# RX.net
KiCad netlist of a schematic drawn in EAGLE
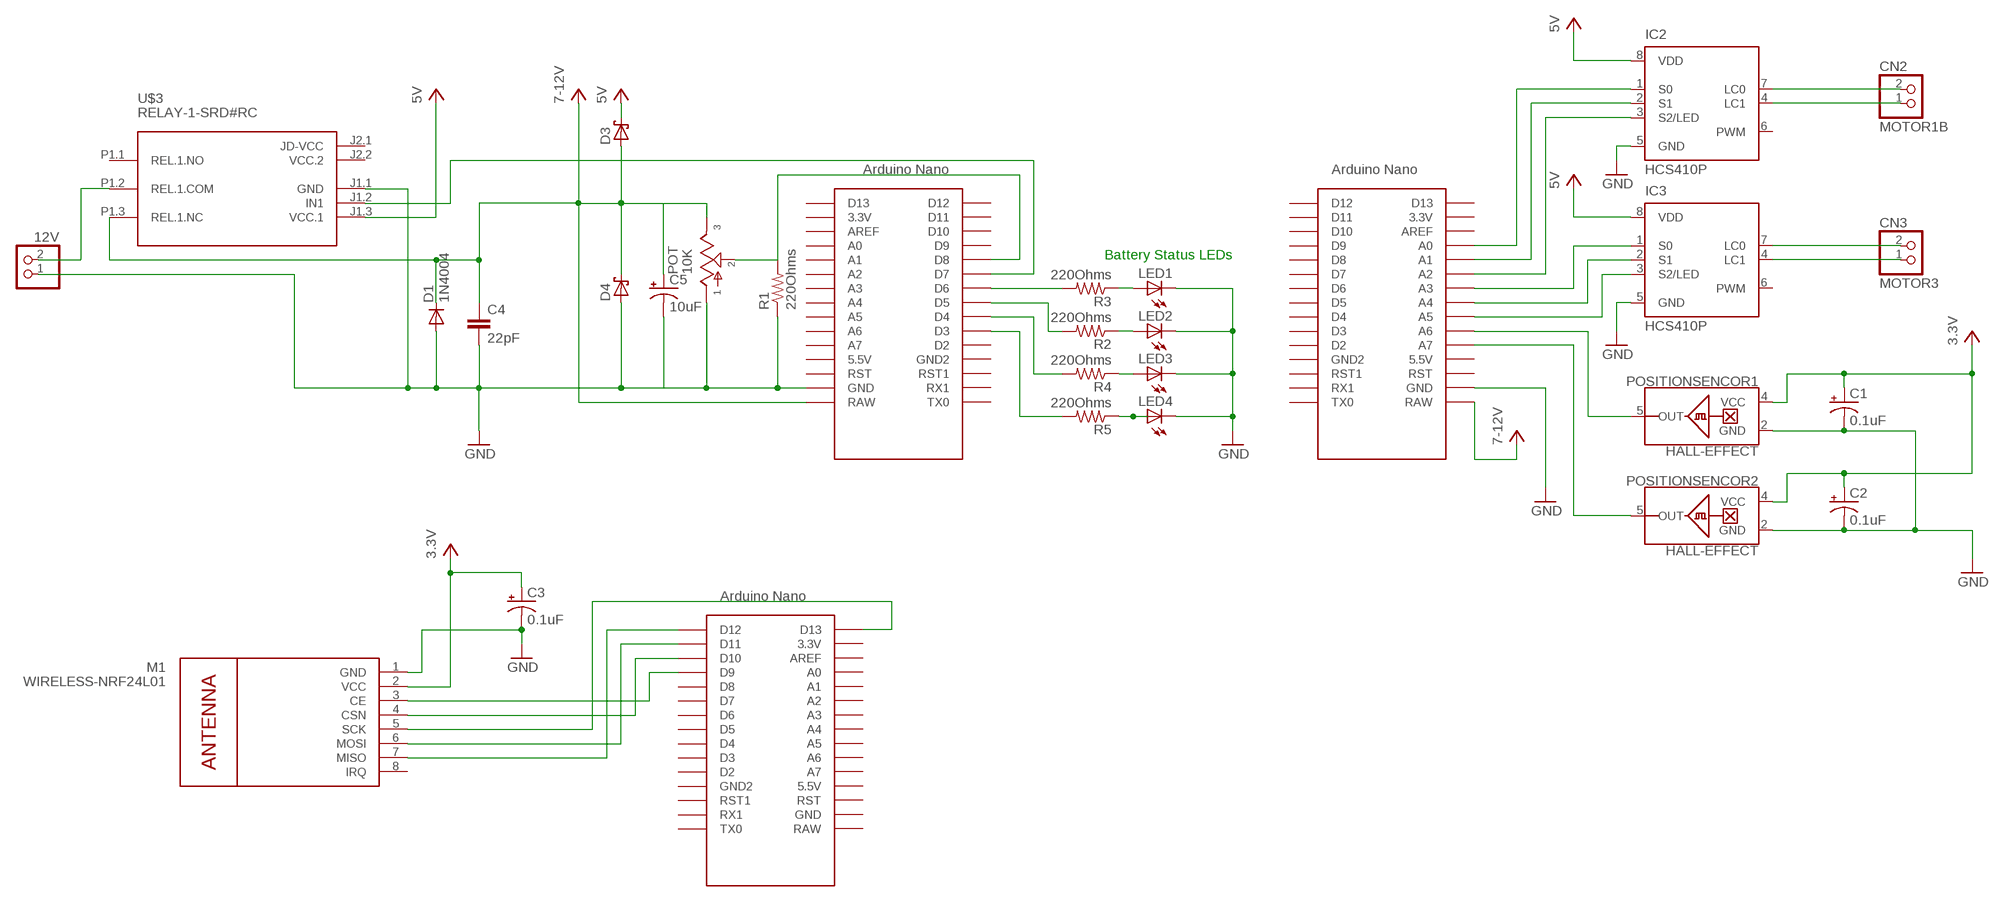
[diagram p0: schematic, sheet 1]

(export (version "E")
  (design (tool "Eeschema 10.0.6"))
  (components
    (comp (ref "12V")
      (value "JST_2PIN-SMT")
      (footprint "eagle-import:JST-PH-2-SMT")
      (libsource (lib "eagle-import") (part "JST_2PIN-SMT"))
    )
    (comp (ref "C1")
      (value "0.1uF")
      (footprint "eagle-import:EIA3216")
      (libsource (lib "eagle-import") (part "CAP_POL1206"))
    )
    (comp (ref "C2")
      (value "0.1uF")
      (footprint "eagle-import:EIA3216")
      (libsource (lib "eagle-import") (part "CAP_POL1206"))
    )
    (comp (ref "C3")
      (value "0.1uF")
      (footprint "eagle-import:EIA3216")
      (libsource (lib "eagle-import") (part "CAP_POL1206"))
    )
    (comp (ref "C4")
      (value "22pF")
      (footprint "eagle-import:C2.5-3")
      (libsource (lib "eagle-import") (part "C2,5-3"))
    )
    (comp (ref "C5")
      (value "10uF")
      (footprint "eagle-import:EIA3216")
      (libsource (lib "eagle-import") (part "CAP_POL1206"))
    )
    (comp (ref "CN2")
      (value "MOTOR1B")
      (footprint "eagle-import:JST-PH-2-SMT")
      (libsource (lib "eagle-import") (part "JST_2PIN-SMT"))
    )
    (comp (ref "CN3")
      (value "MOTOR3")
      (footprint "eagle-import:JST-PH-2-SMT")
      (libsource (lib "eagle-import") (part "JST_2PIN-SMT"))
    )
    (comp (ref "D1")
      (value "1N4004")
      (footprint "eagle-import:DO41-10")
      (libsource (lib "eagle-import") (part "1N4004"))
    )
    (comp (ref "D3")
      (value "SCHOTTKY-DIODEAG")
      (footprint "eagle-import:AG")
      (libsource (lib "eagle-import") (part "SCHOTTKY-DIODEAG"))
    )
    (comp (ref "D4")
      (value "SCHOTTKY-DIODEAG")
      (footprint "eagle-import:AG")
      (libsource (lib "eagle-import") (part "SCHOTTKY-DIODEAG"))
    )
    (comp (ref "IC2")
      (value "HCS410P")
      (footprint "eagle-import:DIL8")
      (fields (field (name "MF") "MICROCHIP") (field (name "MPN") "HCS410-I/P"))
      (libsource (lib "eagle-import") (part "HCS410P"))
    )
    (comp (ref "IC3")
      (value "HCS410P")
      (footprint "eagle-import:DIL8")
      (fields (field (name "MF") "MICROCHIP") (field (name "MPN") "HCS410-I/P"))
      (libsource (lib "eagle-import") (part "HCS410P"))
    )
    (comp (ref "LED1")
      (value "LED")
      (footprint "eagle-import:SMARTLED-TTW")
      (libsource (lib "eagle-import") (part "LED"))
    )
    (comp (ref "LED2")
      (value "LED")
      (footprint "eagle-import:SMARTLED-TTW")
      (libsource (lib "eagle-import") (part "LED"))
    )
    (comp (ref "LED3")
      (value "LED")
      (footprint "eagle-import:SMARTLED-TTW")
      (libsource (lib "eagle-import") (part "LED"))
    )
    (comp (ref "LED4")
      (value "LED")
      (footprint "eagle-import:SMARTLED-TTW")
      (libsource (lib "eagle-import") (part "LED"))
    )
    (comp (ref "M1")
      (value "WIRELESS-NRF24L01")
      (footprint "eagle-import:WIRELESS-NRF24L01")
      (libsource (lib "eagle-import") (part "WIRELESS-NRF24L01"))
    )
    (comp (ref "POSITIONSENCOR1")
      (value "HALL-EFFECT")
      (footprint "eagle-import:SC70")
      (libsource (lib "eagle-import") (part "HALL-EFFECT"))
    )
    (comp (ref "POSITIONSENCOR2")
      (value "HALL-EFFECT")
      (footprint "eagle-import:SC70")
      (libsource (lib "eagle-import") (part "HALL-EFFECT"))
    )
    (comp (ref "POT")
      (value "10K")
      (footprint "eagle-import:POT")
      (libsource (lib "eagle-import") (part "POT"))
    )
    (comp (ref "R1")
      (value "220Ohms")
      (footprint "eagle-import:0204V")
      (libsource (lib "eagle-import") (part "R-US_0204/2V"))
    )
    (comp (ref "R2")
      (value "220Ohms")
      (footprint "eagle-import:0204V")
      (libsource (lib "eagle-import") (part "R-US_0204/2V"))
    )
    (comp (ref "R3")
      (value "220Ohms")
      (footprint "eagle-import:0204V")
      (libsource (lib "eagle-import") (part "R-US_0204/2V"))
    )
    (comp (ref "R4")
      (value "220Ohms")
      (footprint "eagle-import:0204V")
      (libsource (lib "eagle-import") (part "R-US_0204/2V"))
    )
    (comp (ref "R5")
      (value "220Ohms")
      (footprint "eagle-import:0204V")
      (libsource (lib "eagle-import") (part "R-US_0204/2V"))
    )
    (comp (ref "U$1")
      (value "NANO")
      (footprint "eagle-import:NANO")
      (libsource (lib "eagle-import") (part "NANO"))
    )
    (comp (ref "U$2")
      (value "NANO")
      (footprint "eagle-import:NANO")
      (libsource (lib "eagle-import") (part "NANO"))
    )
    (comp (ref "U$3")
      (value "RELAY-1-SRD#RC")
      (footprint "eagle-import:RELAY-1-SRD#RC")
      (libsource (lib "eagle-import") (part "RELAY-1-SRD#RC"))
    )
    (comp (ref "U$4")
      (value "NANO")
      (footprint "eagle-import:NANO")
      (libsource (lib "eagle-import") (part "NANO"))
    )
  )
  (nets
    (net (code "1") (name "/VCC.2") (class "Default")
      (node (ref "U$3") (pin "J2.2") (pinfunction "VCC.2_J2.2") (pintype "power_in"))
    )
    (net (code "2") (name "3.3V") (class "Default")
      (node (ref "C1") (pin "A") (pinfunction "+_A") (pintype "passive"))
      (node (ref "C2") (pin "A") (pinfunction "+_A") (pintype "passive"))
      (node (ref "C3") (pin "A") (pinfunction "+_A") (pintype "passive"))
      (node (ref "C4") (pin "1") (pinfunction "1_1") (pintype "passive"))
      (node (ref "C5") (pin "A") (pinfunction "+_A") (pintype "passive"))
      (node (ref "D1") (pin "C") (pinfunction "C_C") (pintype "passive"))
      (node (ref "D3") (pin "A") (pinfunction "A_A") (pintype "passive"))
      (node (ref "D3") (pin "C") (pinfunction "C_C") (pintype "passive"))
      (node (ref "D4") (pin "C") (pinfunction "C_C") (pintype "passive"))
      (node (ref "IC2") (pin "8") (pinfunction "VDD_8") (pintype "power_in"))
      (node (ref "IC3") (pin "8") (pinfunction "VDD_8") (pintype "power_in"))
      (node (ref "M1") (pin "2") (pinfunction "VCC_2") (pintype "power_in"))
      (node (ref "POSITIONSENCOR1") (pin "4") (pinfunction "VCC_4") (pintype "bidirectional"))
      (node (ref "POSITIONSENCOR2") (pin "4") (pinfunction "VCC_4") (pintype "bidirectional"))
      (node (ref "POT") (pin "3") (pinfunction "3_3") (pintype "passive"))
      (node (ref "U$1") (pin "RAW") (pinfunction "RAW_RAW") (pintype "bidirectional"))
      (node (ref "U$2") (pin "RAW") (pinfunction "RAW_RAW") (pintype "bidirectional"))
      (node (ref "U$3") (pin "J1.3") (pinfunction "VCC.1_J1.3") (pintype "power_in"))
      (node (ref "U$3") (pin "P1.3") (pinfunction "REL.1.NC_P1.3") (pintype "bidirectional"))
    )
    (net (code "3") (name "GND") (class "Default")
      (node (ref "12V") (pin "1") (pinfunction "2_1") (pintype "passive"))
      (node (ref "C1") (pin "C") (pinfunction "-_C") (pintype "passive"))
      (node (ref "C2") (pin "C") (pinfunction "-_C") (pintype "passive"))
      (node (ref "C3") (pin "C") (pinfunction "-_C") (pintype "passive"))
      (node (ref "C4") (pin "2") (pinfunction "2_2") (pintype "passive"))
      (node (ref "C5") (pin "C") (pinfunction "-_C") (pintype "passive"))
      (node (ref "D1") (pin "A") (pinfunction "A_A") (pintype "passive"))
      (node (ref "D4") (pin "A") (pinfunction "A_A") (pintype "passive"))
      (node (ref "IC2") (pin "5") (pinfunction "GND_5") (pintype "power_in"))
      (node (ref "IC3") (pin "5") (pinfunction "GND_5") (pintype "power_in"))
      (node (ref "LED1") (pin "C@1") (pinfunction "C_C@1") (pintype "passive"))
      (node (ref "LED2") (pin "C@1") (pinfunction "C_C@1") (pintype "passive"))
      (node (ref "LED3") (pin "C@1") (pinfunction "C_C@1") (pintype "passive"))
      (node (ref "LED4") (pin "C@1") (pinfunction "C_C@1") (pintype "passive"))
      (node (ref "M1") (pin "1") (pinfunction "GND_1") (pintype "power_in"))
      (node (ref "POSITIONSENCOR1") (pin "2") (pinfunction "GND_2") (pintype "bidirectional"))
      (node (ref "POSITIONSENCOR2") (pin "2") (pinfunction "GND_2") (pintype "bidirectional"))
      (node (ref "POT") (pin "1") (pinfunction "1_1") (pintype "passive"))
      (node (ref "R1") (pin "1") (pinfunction "1_1") (pintype "passive"))
      (node (ref "U$1") (pin "GND") (pinfunction "GND_GND") (pintype "bidirectional"))
      (node (ref "U$2") (pin "GND") (pinfunction "GND_GND") (pintype "bidirectional"))
      (node (ref "U$3") (pin "J1.1") (pinfunction "GND_J1.1") (pintype "power_in"))
    )
    (net (code "4") (name "Net-(12V-1)") (class "Default")
      (node (ref "12V") (pin "2") (pinfunction "1_2") (pintype "passive"))
      (node (ref "U$3") (pin "P1.2") (pinfunction "REL.1.COM_P1.2") (pintype "bidirectional"))
    )
    (net (code "5") (name "Net-(CN2-1)") (class "Default")
      (node (ref "CN2") (pin "2") (pinfunction "1_2") (pintype "passive"))
      (node (ref "IC2") (pin "7") (pinfunction "LC0_7") (pintype "bidirectional"))
    )
    (net (code "6") (name "Net-(CN2-2)") (class "Default")
      (node (ref "CN2") (pin "1") (pinfunction "2_1") (pintype "passive"))
      (node (ref "IC2") (pin "4") (pinfunction "LC1_4") (pintype "bidirectional"))
    )
    (net (code "7") (name "Net-(CN3-1)") (class "Default")
      (node (ref "CN3") (pin "2") (pinfunction "1_2") (pintype "passive"))
      (node (ref "IC3") (pin "7") (pinfunction "LC0_7") (pintype "bidirectional"))
    )
    (net (code "8") (name "Net-(CN3-2)") (class "Default")
      (node (ref "CN3") (pin "1") (pinfunction "2_1") (pintype "passive"))
      (node (ref "IC3") (pin "4") (pinfunction "LC1_4") (pintype "bidirectional"))
    )
    (net (code "9") (name "Net-(IC2-S0)") (class "Default")
      (node (ref "IC2") (pin "1") (pinfunction "S0_1") (pintype "input"))
      (node (ref "U$1") (pin "A0") (pinfunction "A0_A0") (pintype "bidirectional"))
    )
    (net (code "10") (name "Net-(IC2-S1)") (class "Default")
      (node (ref "IC2") (pin "2") (pinfunction "S1_2") (pintype "input"))
      (node (ref "U$1") (pin "A1") (pinfunction "A1_A1") (pintype "bidirectional"))
    )
    (net (code "11") (name "Net-(IC2-S2{slash}LED)") (class "Default")
      (node (ref "IC2") (pin "3") (pinfunction "S2/LED_3") (pintype "bidirectional"))
      (node (ref "U$1") (pin "A2") (pinfunction "A2_A2") (pintype "bidirectional"))
    )
    (net (code "12") (name "Net-(IC3-S0)") (class "Default")
      (node (ref "IC3") (pin "1") (pinfunction "S0_1") (pintype "input"))
      (node (ref "U$1") (pin "A3") (pinfunction "A3_A3") (pintype "bidirectional"))
    )
    (net (code "13") (name "Net-(IC3-S1)") (class "Default")
      (node (ref "IC3") (pin "2") (pinfunction "S1_2") (pintype "input"))
      (node (ref "U$1") (pin "A4") (pinfunction "A4_A4") (pintype "bidirectional"))
    )
    (net (code "14") (name "Net-(IC3-S2{slash}LED)") (class "Default")
      (node (ref "IC3") (pin "3") (pinfunction "S2/LED_3") (pintype "bidirectional"))
      (node (ref "U$1") (pin "A5") (pinfunction "A5_A5") (pintype "bidirectional"))
    )
    (net (code "15") (name "Net-(LED1-A)") (class "Default")
      (node (ref "LED1") (pin "A@1") (pinfunction "A_A@1") (pintype "passive"))
      (node (ref "R3") (pin "1") (pinfunction "1_1") (pintype "passive"))
    )
    (net (code "16") (name "Net-(LED2-A)") (class "Default")
      (node (ref "LED2") (pin "A@1") (pinfunction "A_A@1") (pintype "passive"))
      (node (ref "R2") (pin "1") (pinfunction "1_1") (pintype "passive"))
    )
    (net (code "17") (name "Net-(LED3-A)") (class "Default")
      (node (ref "LED3") (pin "A@1") (pinfunction "A_A@1") (pintype "passive"))
      (node (ref "R4") (pin "1") (pinfunction "1_1") (pintype "passive"))
    )
    (net (code "18") (name "Net-(LED4-A)") (class "Default")
      (node (ref "LED4") (pin "A@1") (pinfunction "A_A@1") (pintype "passive"))
      (node (ref "R5") (pin "1") (pinfunction "1_1") (pintype "passive"))
    )
    (net (code "19") (name "Net-(M1-CE)") (class "Default")
      (node (ref "M1") (pin "3") (pinfunction "CE_3") (pintype "bidirectional"))
      (node (ref "U$4") (pin "D9") (pinfunction "D9_D9") (pintype "bidirectional"))
    )
    (net (code "20") (name "Net-(M1-CSN)") (class "Default")
      (node (ref "M1") (pin "4") (pinfunction "CSN_4") (pintype "bidirectional"))
      (node (ref "U$4") (pin "D10") (pinfunction "D10_D10") (pintype "bidirectional"))
    )
    (net (code "21") (name "Net-(M1-MISO)") (class "Default")
      (node (ref "M1") (pin "7") (pinfunction "MISO_7") (pintype "bidirectional"))
      (node (ref "U$4") (pin "D12") (pinfunction "D12_D12") (pintype "bidirectional"))
    )
    (net (code "22") (name "Net-(M1-MOSI)") (class "Default")
      (node (ref "M1") (pin "6") (pinfunction "MOSI_6") (pintype "bidirectional"))
      (node (ref "U$4") (pin "D11") (pinfunction "D11_D11") (pintype "bidirectional"))
    )
    (net (code "23") (name "Net-(M1-SCK)") (class "Default")
      (node (ref "M1") (pin "5") (pinfunction "SCK_5") (pintype "bidirectional"))
      (node (ref "U$4") (pin "D13") (pinfunction "D13_D13") (pintype "bidirectional"))
    )
    (net (code "24") (name "Net-(POSITIONSENCOR1-OUT)") (class "Default")
      (node (ref "POSITIONSENCOR1") (pin "5") (pinfunction "OUT_5") (pintype "bidirectional"))
      (node (ref "U$1") (pin "A6") (pinfunction "A6_A6") (pintype "bidirectional"))
    )
    (net (code "25") (name "Net-(POSITIONSENCOR2-OUT)") (class "Default")
      (node (ref "POSITIONSENCOR2") (pin "5") (pinfunction "OUT_5") (pintype "bidirectional"))
      (node (ref "U$1") (pin "A7") (pinfunction "A7_A7") (pintype "bidirectional"))
    )
    (net (code "26") (name "Net-(POT-Pad2)") (class "Default")
      (node (ref "POT") (pin "2") (pinfunction "2_2") (pintype "passive"))
      (node (ref "R1") (pin "2") (pinfunction "2_2") (pintype "passive"))
      (node (ref "U$2") (pin "D8") (pinfunction "D8_D8") (pintype "bidirectional"))
    )
    (net (code "27") (name "Net-(R2-Pad2)") (class "Default")
      (node (ref "R2") (pin "2") (pinfunction "2_2") (pintype "passive"))
      (node (ref "U$2") (pin "D5") (pinfunction "D5_D5") (pintype "bidirectional"))
    )
    (net (code "28") (name "Net-(R3-Pad2)") (class "Default")
      (node (ref "R3") (pin "2") (pinfunction "2_2") (pintype "passive"))
      (node (ref "U$2") (pin "D6") (pinfunction "D6_D6") (pintype "bidirectional"))
    )
    (net (code "29") (name "Net-(R4-Pad2)") (class "Default")
      (node (ref "R4") (pin "2") (pinfunction "2_2") (pintype "passive"))
      (node (ref "U$2") (pin "D4") (pinfunction "D4_D4") (pintype "bidirectional"))
    )
    (net (code "30") (name "Net-(R5-Pad2)") (class "Default")
      (node (ref "R5") (pin "2") (pinfunction "2_2") (pintype "passive"))
      (node (ref "U$2") (pin "D3") (pinfunction "D3_D3") (pintype "bidirectional"))
    )
    (net (code "31") (name "Net-(U$3-IN1)") (class "Default")
      (node (ref "U$2") (pin "D7") (pinfunction "D7_D7") (pintype "bidirectional"))
      (node (ref "U$3") (pin "J1.2") (pinfunction "IN1_J1.2") (pintype "bidirectional"))
    )
    (net (code "32") (name "unconnected-(IC2-PWM-Pad6)") (class "Default")
      (node (ref "IC2") (pin "6") (pinfunction "PWM_6") (pintype "bidirectional"))
    )
    (net (code "33") (name "unconnected-(IC3-PWM-Pad6)") (class "Default")
      (node (ref "IC3") (pin "6") (pinfunction "PWM_6") (pintype "bidirectional"))
    )
    (net (code "34") (name "unconnected-(M1-IRQ-Pad8)") (class "Default")
      (node (ref "M1") (pin "8") (pinfunction "IRQ_8") (pintype "bidirectional"))
    )
    (net (code "35") (name "unconnected-(U$1-5.5V-Pad5V)") (class "Default")
      (node (ref "U$1") (pin "5V") (pinfunction "5.5V_5V") (pintype "bidirectional"))
    )
    (net (code "36") (name "unconnected-(U$1-GND2-PadGND1)") (class "Default")
      (node (ref "U$1") (pin "GND1") (pinfunction "GND2_GND1") (pintype "bidirectional"))
    )
    (net (code "37") (name "unconnected-(U$1-Pad3.3V)") (class "Default")
      (node (ref "U$1") (pin "3.3V") (pinfunction "3.3V_3.3V") (pintype "bidirectional"))
    )
    (net (code "38") (name "unconnected-(U$1-PadAREF)") (class "Default")
      (node (ref "U$1") (pin "AREF") (pinfunction "AREF_AREF") (pintype "bidirectional"))
    )
    (net (code "39") (name "unconnected-(U$1-PadD2)") (class "Default")
      (node (ref "U$1") (pin "D2") (pinfunction "D2_D2") (pintype "bidirectional"))
    )
    (net (code "40") (name "unconnected-(U$1-PadD3)") (class "Default")
      (node (ref "U$1") (pin "D3") (pinfunction "D3_D3") (pintype "bidirectional"))
    )
    (net (code "41") (name "unconnected-(U$1-PadD4)") (class "Default")
      (node (ref "U$1") (pin "D4") (pinfunction "D4_D4") (pintype "bidirectional"))
    )
    (net (code "42") (name "unconnected-(U$1-PadD5)") (class "Default")
      (node (ref "U$1") (pin "D5") (pinfunction "D5_D5") (pintype "bidirectional"))
    )
    (net (code "43") (name "unconnected-(U$1-PadD6)") (class "Default")
      (node (ref "U$1") (pin "D6") (pinfunction "D6_D6") (pintype "bidirectional"))
    )
    (net (code "44") (name "unconnected-(U$1-PadD7)") (class "Default")
      (node (ref "U$1") (pin "D7") (pinfunction "D7_D7") (pintype "bidirectional"))
    )
    (net (code "45") (name "unconnected-(U$1-PadD8)") (class "Default")
      (node (ref "U$1") (pin "D8") (pinfunction "D8_D8") (pintype "bidirectional"))
    )
    (net (code "46") (name "unconnected-(U$1-PadD9)") (class "Default")
      (node (ref "U$1") (pin "D9") (pinfunction "D9_D9") (pintype "bidirectional"))
    )
    (net (code "47") (name "unconnected-(U$1-PadD10)") (class "Default")
      (node (ref "U$1") (pin "D10") (pinfunction "D10_D10") (pintype "bidirectional"))
    )
    (net (code "48") (name "unconnected-(U$1-PadD11)") (class "Default")
      (node (ref "U$1") (pin "D11") (pinfunction "D11_D11") (pintype "bidirectional"))
    )
    (net (code "49") (name "unconnected-(U$1-PadD12)") (class "Default")
      (node (ref "U$1") (pin "D12") (pinfunction "D12_D12") (pintype "bidirectional"))
    )
    (net (code "50") (name "unconnected-(U$1-PadD13)") (class "Default")
      (node (ref "U$1") (pin "D13") (pinfunction "D13_D13") (pintype "bidirectional"))
    )
    (net (code "51") (name "unconnected-(U$1-PadICSP1)") (class "Default")
      (node (ref "U$1") (pin "ICSP1") (pinfunction "ICSP1_ICSP1") (pintype "bidirectional"))
    )
    (net (code "52") (name "unconnected-(U$1-PadICSP2)") (class "Default")
      (node (ref "U$1") (pin "ICSP2") (pinfunction "ICSP2_ICSP2") (pintype "bidirectional"))
    )
    (net (code "53") (name "unconnected-(U$1-PadICSP3)") (class "Default")
      (node (ref "U$1") (pin "ICSP3") (pinfunction "ICSP3_ICSP3") (pintype "bidirectional"))
    )
    (net (code "54") (name "unconnected-(U$1-PadICSP4)") (class "Default")
      (node (ref "U$1") (pin "ICSP4") (pinfunction "ICSP4_ICSP4") (pintype "bidirectional"))
    )
    (net (code "55") (name "unconnected-(U$1-PadICSP5)") (class "Default")
      (node (ref "U$1") (pin "ICSP5") (pinfunction "ICSP5_ICSP5") (pintype "bidirectional"))
    )
    (net (code "56") (name "unconnected-(U$1-PadICSP6)") (class "Default")
      (node (ref "U$1") (pin "ICSP6") (pinfunction "ICSP6_ICSP6") (pintype "bidirectional"))
    )
    (net (code "57") (name "unconnected-(U$1-PadRST)") (class "Default")
      (node (ref "U$1") (pin "RST") (pinfunction "RST_RST") (pintype "bidirectional"))
    )
    (net (code "58") (name "unconnected-(U$1-PadRST1)") (class "Default")
      (node (ref "U$1") (pin "RST1") (pinfunction "RST1_RST1") (pintype "bidirectional"))
    )
    (net (code "59") (name "unconnected-(U$1-PadRX1)") (class "Default")
      (node (ref "U$1") (pin "RX1") (pinfunction "RX1_RX1") (pintype "bidirectional"))
    )
    (net (code "60") (name "unconnected-(U$1-PadTX0)") (class "Default")
      (node (ref "U$1") (pin "TX0") (pinfunction "TX0_TX0") (pintype "bidirectional"))
    )
    (net (code "61") (name "unconnected-(U$2-5.5V-Pad5V)") (class "Default")
      (node (ref "U$2") (pin "5V") (pinfunction "5.5V_5V") (pintype "bidirectional"))
    )
    (net (code "62") (name "unconnected-(U$2-GND2-PadGND1)") (class "Default")
      (node (ref "U$2") (pin "GND1") (pinfunction "GND2_GND1") (pintype "bidirectional"))
    )
    (net (code "63") (name "unconnected-(U$2-Pad3.3V)") (class "Default")
      (node (ref "U$2") (pin "3.3V") (pinfunction "3.3V_3.3V") (pintype "bidirectional"))
    )
    (net (code "64") (name "unconnected-(U$2-PadA0)") (class "Default")
      (node (ref "U$2") (pin "A0") (pinfunction "A0_A0") (pintype "bidirectional"))
    )
    (net (code "65") (name "unconnected-(U$2-PadA1)") (class "Default")
      (node (ref "U$2") (pin "A1") (pinfunction "A1_A1") (pintype "bidirectional"))
    )
    (net (code "66") (name "unconnected-(U$2-PadA2)") (class "Default")
      (node (ref "U$2") (pin "A2") (pinfunction "A2_A2") (pintype "bidirectional"))
    )
    (net (code "67") (name "unconnected-(U$2-PadA3)") (class "Default")
      (node (ref "U$2") (pin "A3") (pinfunction "A3_A3") (pintype "bidirectional"))
    )
    (net (code "68") (name "unconnected-(U$2-PadA4)") (class "Default")
      (node (ref "U$2") (pin "A4") (pinfunction "A4_A4") (pintype "bidirectional"))
    )
    (net (code "69") (name "unconnected-(U$2-PadA5)") (class "Default")
      (node (ref "U$2") (pin "A5") (pinfunction "A5_A5") (pintype "bidirectional"))
    )
    (net (code "70") (name "unconnected-(U$2-PadA6)") (class "Default")
      (node (ref "U$2") (pin "A6") (pinfunction "A6_A6") (pintype "bidirectional"))
    )
    (net (code "71") (name "unconnected-(U$2-PadA7)") (class "Default")
      (node (ref "U$2") (pin "A7") (pinfunction "A7_A7") (pintype "bidirectional"))
    )
    (net (code "72") (name "unconnected-(U$2-PadAREF)") (class "Default")
      (node (ref "U$2") (pin "AREF") (pinfunction "AREF_AREF") (pintype "bidirectional"))
    )
    (net (code "73") (name "unconnected-(U$2-PadD2)") (class "Default")
      (node (ref "U$2") (pin "D2") (pinfunction "D2_D2") (pintype "bidirectional"))
    )
    (net (code "74") (name "unconnected-(U$2-PadD9)") (class "Default")
      (node (ref "U$2") (pin "D9") (pinfunction "D9_D9") (pintype "bidirectional"))
    )
    (net (code "75") (name "unconnected-(U$2-PadD10)") (class "Default")
      (node (ref "U$2") (pin "D10") (pinfunction "D10_D10") (pintype "bidirectional"))
    )
    (net (code "76") (name "unconnected-(U$2-PadD11)") (class "Default")
      (node (ref "U$2") (pin "D11") (pinfunction "D11_D11") (pintype "bidirectional"))
    )
    (net (code "77") (name "unconnected-(U$2-PadD12)") (class "Default")
      (node (ref "U$2") (pin "D12") (pinfunction "D12_D12") (pintype "bidirectional"))
    )
    (net (code "78") (name "unconnected-(U$2-PadD13)") (class "Default")
      (node (ref "U$2") (pin "D13") (pinfunction "D13_D13") (pintype "bidirectional"))
    )
    (net (code "79") (name "unconnected-(U$2-PadICSP1)") (class "Default")
      (node (ref "U$2") (pin "ICSP1") (pinfunction "ICSP1_ICSP1") (pintype "bidirectional"))
    )
    (net (code "80") (name "unconnected-(U$2-PadICSP2)") (class "Default")
      (node (ref "U$2") (pin "ICSP2") (pinfunction "ICSP2_ICSP2") (pintype "bidirectional"))
    )
    (net (code "81") (name "unconnected-(U$2-PadICSP3)") (class "Default")
      (node (ref "U$2") (pin "ICSP3") (pinfunction "ICSP3_ICSP3") (pintype "bidirectional"))
    )
    (net (code "82") (name "unconnected-(U$2-PadICSP4)") (class "Default")
      (node (ref "U$2") (pin "ICSP4") (pinfunction "ICSP4_ICSP4") (pintype "bidirectional"))
    )
    (net (code "83") (name "unconnected-(U$2-PadICSP5)") (class "Default")
      (node (ref "U$2") (pin "ICSP5") (pinfunction "ICSP5_ICSP5") (pintype "bidirectional"))
    )
    (net (code "84") (name "unconnected-(U$2-PadICSP6)") (class "Default")
      (node (ref "U$2") (pin "ICSP6") (pinfunction "ICSP6_ICSP6") (pintype "bidirectional"))
    )
    (net (code "85") (name "unconnected-(U$2-PadRST)") (class "Default")
      (node (ref "U$2") (pin "RST") (pinfunction "RST_RST") (pintype "bidirectional"))
    )
    (net (code "86") (name "unconnected-(U$2-PadRST1)") (class "Default")
      (node (ref "U$2") (pin "RST1") (pinfunction "RST1_RST1") (pintype "bidirectional"))
    )
    (net (code "87") (name "unconnected-(U$2-PadRX1)") (class "Default")
      (node (ref "U$2") (pin "RX1") (pinfunction "RX1_RX1") (pintype "bidirectional"))
    )
    (net (code "88") (name "unconnected-(U$2-PadTX0)") (class "Default")
      (node (ref "U$2") (pin "TX0") (pinfunction "TX0_TX0") (pintype "bidirectional"))
    )
    (net (code "89") (name "unconnected-(U$3-JD-VCC-PadJ2.1)") (class "Default")
      (node (ref "U$3") (pin "J2.1") (pinfunction "JD-VCC_J2.1") (pintype "bidirectional"))
    )
    (net (code "90") (name "unconnected-(U$3-REL.1.NO-PadP1.1)") (class "Default")
      (node (ref "U$3") (pin "P1.1") (pinfunction "REL.1.NO_P1.1") (pintype "bidirectional"))
    )
    (net (code "91") (name "unconnected-(U$4-5.5V-Pad5V)") (class "Default")
      (node (ref "U$4") (pin "5V") (pinfunction "5.5V_5V") (pintype "bidirectional"))
    )
    (net (code "92") (name "unconnected-(U$4-GND2-PadGND1)") (class "Default")
      (node (ref "U$4") (pin "GND1") (pinfunction "GND2_GND1") (pintype "bidirectional"))
    )
    (net (code "93") (name "unconnected-(U$4-Pad3.3V)") (class "Default")
      (node (ref "U$4") (pin "3.3V") (pinfunction "3.3V_3.3V") (pintype "bidirectional"))
    )
    (net (code "94") (name "unconnected-(U$4-PadA0)") (class "Default")
      (node (ref "U$4") (pin "A0") (pinfunction "A0_A0") (pintype "bidirectional"))
    )
    (net (code "95") (name "unconnected-(U$4-PadA1)") (class "Default")
      (node (ref "U$4") (pin "A1") (pinfunction "A1_A1") (pintype "bidirectional"))
    )
    (net (code "96") (name "unconnected-(U$4-PadA2)") (class "Default")
      (node (ref "U$4") (pin "A2") (pinfunction "A2_A2") (pintype "bidirectional"))
    )
    (net (code "97") (name "unconnected-(U$4-PadA3)") (class "Default")
      (node (ref "U$4") (pin "A3") (pinfunction "A3_A3") (pintype "bidirectional"))
    )
    (net (code "98") (name "unconnected-(U$4-PadA4)") (class "Default")
      (node (ref "U$4") (pin "A4") (pinfunction "A4_A4") (pintype "bidirectional"))
    )
    (net (code "99") (name "unconnected-(U$4-PadA5)") (class "Default")
      (node (ref "U$4") (pin "A5") (pinfunction "A5_A5") (pintype "bidirectional"))
    )
    (net (code "100") (name "unconnected-(U$4-PadA6)") (class "Default")
      (node (ref "U$4") (pin "A6") (pinfunction "A6_A6") (pintype "bidirectional"))
    )
    (net (code "101") (name "unconnected-(U$4-PadA7)") (class "Default")
      (node (ref "U$4") (pin "A7") (pinfunction "A7_A7") (pintype "bidirectional"))
    )
    (net (code "102") (name "unconnected-(U$4-PadAREF)") (class "Default")
      (node (ref "U$4") (pin "AREF") (pinfunction "AREF_AREF") (pintype "bidirectional"))
    )
    (net (code "103") (name "unconnected-(U$4-PadD2)") (class "Default")
      (node (ref "U$4") (pin "D2") (pinfunction "D2_D2") (pintype "bidirectional"))
    )
    (net (code "104") (name "unconnected-(U$4-PadD3)") (class "Default")
      (node (ref "U$4") (pin "D3") (pinfunction "D3_D3") (pintype "bidirectional"))
    )
    (net (code "105") (name "unconnected-(U$4-PadD4)") (class "Default")
      (node (ref "U$4") (pin "D4") (pinfunction "D4_D4") (pintype "bidirectional"))
    )
    (net (code "106") (name "unconnected-(U$4-PadD5)") (class "Default")
      (node (ref "U$4") (pin "D5") (pinfunction "D5_D5") (pintype "bidirectional"))
    )
    (net (code "107") (name "unconnected-(U$4-PadD6)") (class "Default")
      (node (ref "U$4") (pin "D6") (pinfunction "D6_D6") (pintype "bidirectional"))
    )
    (net (code "108") (name "unconnected-(U$4-PadD7)") (class "Default")
      (node (ref "U$4") (pin "D7") (pinfunction "D7_D7") (pintype "bidirectional"))
    )
    (net (code "109") (name "unconnected-(U$4-PadD8)") (class "Default")
      (node (ref "U$4") (pin "D8") (pinfunction "D8_D8") (pintype "bidirectional"))
    )
    (net (code "110") (name "unconnected-(U$4-PadGND)") (class "Default")
      (node (ref "U$4") (pin "GND") (pinfunction "GND_GND") (pintype "bidirectional"))
    )
    (net (code "111") (name "unconnected-(U$4-PadICSP1)") (class "Default")
      (node (ref "U$4") (pin "ICSP1") (pinfunction "ICSP1_ICSP1") (pintype "bidirectional"))
    )
    (net (code "112") (name "unconnected-(U$4-PadICSP2)") (class "Default")
      (node (ref "U$4") (pin "ICSP2") (pinfunction "ICSP2_ICSP2") (pintype "bidirectional"))
    )
    (net (code "113") (name "unconnected-(U$4-PadICSP3)") (class "Default")
      (node (ref "U$4") (pin "ICSP3") (pinfunction "ICSP3_ICSP3") (pintype "bidirectional"))
    )
    (net (code "114") (name "unconnected-(U$4-PadICSP4)") (class "Default")
      (node (ref "U$4") (pin "ICSP4") (pinfunction "ICSP4_ICSP4") (pintype "bidirectional"))
    )
    (net (code "115") (name "unconnected-(U$4-PadICSP5)") (class "Default")
      (node (ref "U$4") (pin "ICSP5") (pinfunction "ICSP5_ICSP5") (pintype "bidirectional"))
    )
    (net (code "116") (name "unconnected-(U$4-PadICSP6)") (class "Default")
      (node (ref "U$4") (pin "ICSP6") (pinfunction "ICSP6_ICSP6") (pintype "bidirectional"))
    )
    (net (code "117") (name "unconnected-(U$4-PadRAW)") (class "Default")
      (node (ref "U$4") (pin "RAW") (pinfunction "RAW_RAW") (pintype "bidirectional"))
    )
    (net (code "118") (name "unconnected-(U$4-PadRST)") (class "Default")
      (node (ref "U$4") (pin "RST") (pinfunction "RST_RST") (pintype "bidirectional"))
    )
    (net (code "119") (name "unconnected-(U$4-PadRST1)") (class "Default")
      (node (ref "U$4") (pin "RST1") (pinfunction "RST1_RST1") (pintype "bidirectional"))
    )
    (net (code "120") (name "unconnected-(U$4-PadRX1)") (class "Default")
      (node (ref "U$4") (pin "RX1") (pinfunction "RX1_RX1") (pintype "bidirectional"))
    )
    (net (code "121") (name "unconnected-(U$4-PadTX0)") (class "Default")
      (node (ref "U$4") (pin "TX0") (pinfunction "TX0_TX0") (pintype "bidirectional"))
    )
  )
)
